# SH_input_2.net
KiCad netlist of a schematic drawn in EasyEDA
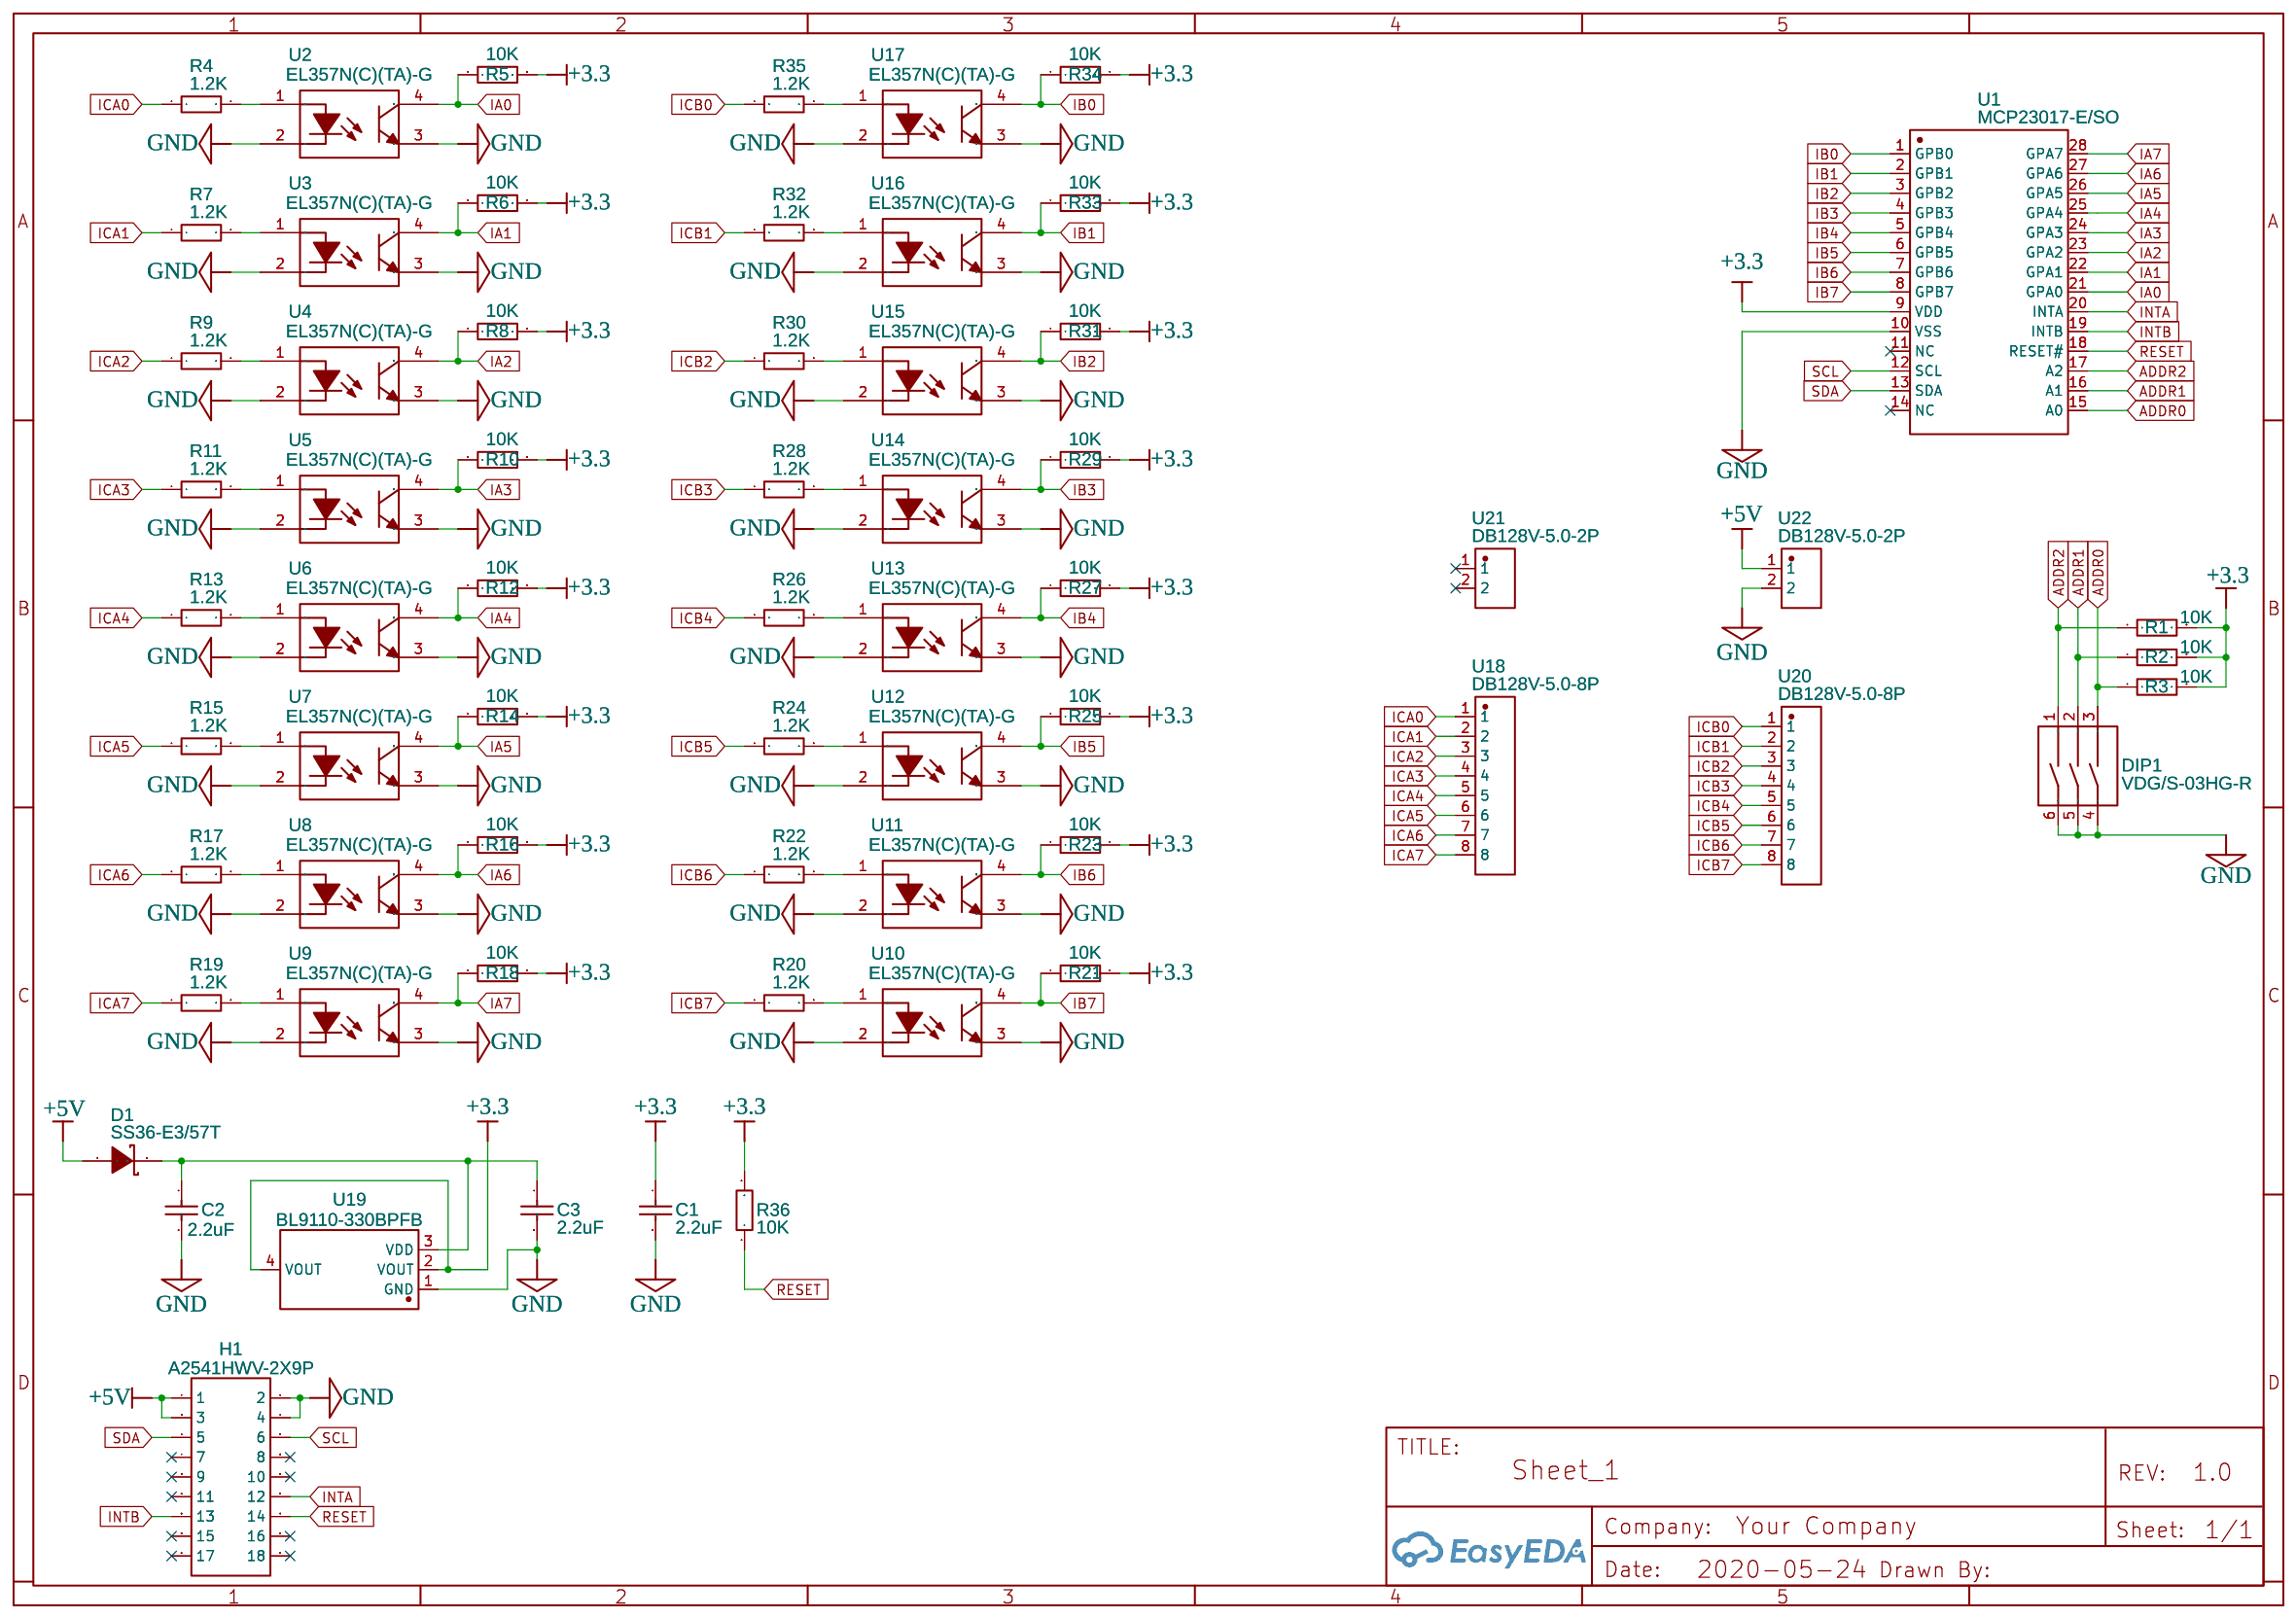
[diagram p0: schematic sheet]

(export (version "E")
  (design (tool "Eeschema 10.0.6"))
  (components
    (comp (ref "C1")
      (value "2.2uF")
      (fields
        (field (name "BOM_Manufacturer Part") "CL31B225KBHNNNE")
        (field (name "BOM_Supplier Part") "C50254")
      )
      (libsource (lib "") (part "CL31B225KBHNNNE"))
    )
    (comp (ref "C2")
      (value "2.2uF")
      (fields
        (field (name "BOM_Manufacturer Part") "CL31B225KBHNNNE")
        (field (name "BOM_Supplier Part") "C50254")
      )
      (libsource (lib "") (part "CL31B225KBHNNNE"))
    )
    (comp (ref "C3")
      (value "2.2uF")
      (fields
        (field (name "BOM_Manufacturer Part") "CL31B225KBHNNNE")
        (field (name "BOM_Supplier Part") "C50254")
      )
      (libsource (lib "") (part "CL31B225KBHNNNE"))
    )
    (comp (ref "D1")
      (value "SS36-E3/57T")
      (fields (field (name "BOM_Supplier Part") "C35722"))
      (libsource (lib "") (part "SS36-E3/57T"))
    )
    (comp (ref "DIP1")
      (value "VDG/S-03HG-R")
      (fields (field (name "BOM_Supplier Part") "C52648"))
      (libsource (lib "") (part "VDG/S-03HG-R"))
    )
    (comp (ref "H1")
      (value "A2541HWV-2X9P")
      (fields
        (field (name "BOM_Manufacturer Part") "A2541HWV-2x9P")
        (field (name "BOM_Supplier Part") "C239349")
      )
      (libsource (lib "") (part "A2541HWV-2X9P"))
    )
    (comp (ref "R1")
      (value "10K")
      (fields
        (field (name "BOM_Manufacturer Part") "0603WAF1002T5E")
        (field (name "BOM_Supplier Part") "C25804")
      )
      (libsource (lib "") (part "0603WAF1002T5E"))
    )
    (comp (ref "R2")
      (value "10K")
      (fields
        (field (name "BOM_Manufacturer Part") "0603WAF1002T5E")
        (field (name "BOM_Supplier Part") "C25804")
      )
      (libsource (lib "") (part "0603WAF1002T5E"))
    )
    (comp (ref "R3")
      (value "10K")
      (fields
        (field (name "BOM_Manufacturer Part") "0603WAF1002T5E")
        (field (name "BOM_Supplier Part") "C25804")
      )
      (libsource (lib "") (part "0603WAF1002T5E"))
    )
    (comp (ref "R4")
      (value "1.2K")
      (fields
        (field (name "BOM_Manufacturer Part") "0603WAF1201T5E")
        (field (name "BOM_Supplier Part") "C22765")
      )
      (libsource (lib "") (part "0603WAF1201T5E"))
    )
    (comp (ref "R5")
      (value "10K")
      (fields
        (field (name "BOM_Manufacturer Part") "0603WAF1002T5E")
        (field (name "BOM_Supplier Part") "C25804")
      )
      (libsource (lib "") (part "0603WAF1002T5E"))
    )
    (comp (ref "R6")
      (value "10K")
      (fields
        (field (name "BOM_Manufacturer Part") "0603WAF1002T5E")
        (field (name "BOM_Supplier Part") "C25804")
      )
      (libsource (lib "") (part "0603WAF1002T5E"))
    )
    (comp (ref "R7")
      (value "1.2K")
      (fields
        (field (name "BOM_Manufacturer Part") "0603WAF1201T5E")
        (field (name "BOM_Supplier Part") "C22765")
      )
      (libsource (lib "") (part "0603WAF1201T5E"))
    )
    (comp (ref "R8")
      (value "10K")
      (fields
        (field (name "BOM_Manufacturer Part") "0603WAF1002T5E")
        (field (name "BOM_Supplier Part") "C25804")
      )
      (libsource (lib "") (part "0603WAF1002T5E"))
    )
    (comp (ref "R9")
      (value "1.2K")
      (fields
        (field (name "BOM_Manufacturer Part") "0603WAF1201T5E")
        (field (name "BOM_Supplier Part") "C22765")
      )
      (libsource (lib "") (part "0603WAF1201T5E"))
    )
    (comp (ref "R10")
      (value "10K")
      (fields
        (field (name "BOM_Manufacturer Part") "0603WAF1002T5E")
        (field (name "BOM_Supplier Part") "C25804")
      )
      (libsource (lib "") (part "0603WAF1002T5E"))
    )
    (comp (ref "R11")
      (value "1.2K")
      (fields
        (field (name "BOM_Manufacturer Part") "0603WAF1201T5E")
        (field (name "BOM_Supplier Part") "C22765")
      )
      (libsource (lib "") (part "0603WAF1201T5E"))
    )
    (comp (ref "R12")
      (value "10K")
      (fields
        (field (name "BOM_Manufacturer Part") "0603WAF1002T5E")
        (field (name "BOM_Supplier Part") "C25804")
      )
      (libsource (lib "") (part "0603WAF1002T5E"))
    )
    (comp (ref "R13")
      (value "1.2K")
      (fields
        (field (name "BOM_Manufacturer Part") "0603WAF1201T5E")
        (field (name "BOM_Supplier Part") "C22765")
      )
      (libsource (lib "") (part "0603WAF1201T5E"))
    )
    (comp (ref "R14")
      (value "10K")
      (fields
        (field (name "BOM_Manufacturer Part") "0603WAF1002T5E")
        (field (name "BOM_Supplier Part") "C25804")
      )
      (libsource (lib "") (part "0603WAF1002T5E"))
    )
    (comp (ref "R15")
      (value "1.2K")
      (fields
        (field (name "BOM_Manufacturer Part") "0603WAF1201T5E")
        (field (name "BOM_Supplier Part") "C22765")
      )
      (libsource (lib "") (part "0603WAF1201T5E"))
    )
    (comp (ref "R16")
      (value "10K")
      (fields
        (field (name "BOM_Manufacturer Part") "0603WAF1002T5E")
        (field (name "BOM_Supplier Part") "C25804")
      )
      (libsource (lib "") (part "0603WAF1002T5E"))
    )
    (comp (ref "R17")
      (value "1.2K")
      (fields
        (field (name "BOM_Manufacturer Part") "0603WAF1201T5E")
        (field (name "BOM_Supplier Part") "C22765")
      )
      (libsource (lib "") (part "0603WAF1201T5E"))
    )
    (comp (ref "R18")
      (value "10K")
      (fields
        (field (name "BOM_Manufacturer Part") "0603WAF1002T5E")
        (field (name "BOM_Supplier Part") "C25804")
      )
      (libsource (lib "") (part "0603WAF1002T5E"))
    )
    (comp (ref "R19")
      (value "1.2K")
      (fields
        (field (name "BOM_Manufacturer Part") "0603WAF1201T5E")
        (field (name "BOM_Supplier Part") "C22765")
      )
      (libsource (lib "") (part "0603WAF1201T5E"))
    )
    (comp (ref "R20")
      (value "1.2K")
      (fields
        (field (name "BOM_Manufacturer Part") "0603WAF1201T5E")
        (field (name "BOM_Supplier Part") "C22765")
      )
      (libsource (lib "") (part "0603WAF1201T5E"))
    )
    (comp (ref "R21")
      (value "10K")
      (fields
        (field (name "BOM_Manufacturer Part") "0603WAF1002T5E")
        (field (name "BOM_Supplier Part") "C25804")
      )
      (libsource (lib "") (part "0603WAF1002T5E"))
    )
    (comp (ref "R22")
      (value "1.2K")
      (fields
        (field (name "BOM_Manufacturer Part") "0603WAF1201T5E")
        (field (name "BOM_Supplier Part") "C22765")
      )
      (libsource (lib "") (part "0603WAF1201T5E"))
    )
    (comp (ref "R23")
      (value "10K")
      (fields
        (field (name "BOM_Manufacturer Part") "0603WAF1002T5E")
        (field (name "BOM_Supplier Part") "C25804")
      )
      (libsource (lib "") (part "0603WAF1002T5E"))
    )
    (comp (ref "R24")
      (value "1.2K")
      (fields
        (field (name "BOM_Manufacturer Part") "0603WAF1201T5E")
        (field (name "BOM_Supplier Part") "C22765")
      )
      (libsource (lib "") (part "0603WAF1201T5E"))
    )
    (comp (ref "R25")
      (value "10K")
      (fields
        (field (name "BOM_Manufacturer Part") "0603WAF1002T5E")
        (field (name "BOM_Supplier Part") "C25804")
      )
      (libsource (lib "") (part "0603WAF1002T5E"))
    )
    (comp (ref "R26")
      (value "1.2K")
      (fields
        (field (name "BOM_Manufacturer Part") "0603WAF1201T5E")
        (field (name "BOM_Supplier Part") "C22765")
      )
      (libsource (lib "") (part "0603WAF1201T5E"))
    )
    (comp (ref "R27")
      (value "10K")
      (fields
        (field (name "BOM_Manufacturer Part") "0603WAF1002T5E")
        (field (name "BOM_Supplier Part") "C25804")
      )
      (libsource (lib "") (part "0603WAF1002T5E"))
    )
    (comp (ref "R28")
      (value "1.2K")
      (fields
        (field (name "BOM_Manufacturer Part") "0603WAF1201T5E")
        (field (name "BOM_Supplier Part") "C22765")
      )
      (libsource (lib "") (part "0603WAF1201T5E"))
    )
    (comp (ref "R29")
      (value "10K")
      (fields
        (field (name "BOM_Manufacturer Part") "0603WAF1002T5E")
        (field (name "BOM_Supplier Part") "C25804")
      )
      (libsource (lib "") (part "0603WAF1002T5E"))
    )
    (comp (ref "R30")
      (value "1.2K")
      (fields
        (field (name "BOM_Manufacturer Part") "0603WAF1201T5E")
        (field (name "BOM_Supplier Part") "C22765")
      )
      (libsource (lib "") (part "0603WAF1201T5E"))
    )
    (comp (ref "R31")
      (value "10K")
      (fields
        (field (name "BOM_Manufacturer Part") "0603WAF1002T5E")
        (field (name "BOM_Supplier Part") "C25804")
      )
      (libsource (lib "") (part "0603WAF1002T5E"))
    )
    (comp (ref "R32")
      (value "1.2K")
      (fields
        (field (name "BOM_Manufacturer Part") "0603WAF1201T5E")
        (field (name "BOM_Supplier Part") "C22765")
      )
      (libsource (lib "") (part "0603WAF1201T5E"))
    )
    (comp (ref "R33")
      (value "10K")
      (fields
        (field (name "BOM_Manufacturer Part") "0603WAF1002T5E")
        (field (name "BOM_Supplier Part") "C25804")
      )
      (libsource (lib "") (part "0603WAF1002T5E"))
    )
    (comp (ref "R34")
      (value "10K")
      (fields
        (field (name "BOM_Manufacturer Part") "0603WAF1002T5E")
        (field (name "BOM_Supplier Part") "C25804")
      )
      (libsource (lib "") (part "0603WAF1002T5E"))
    )
    (comp (ref "R35")
      (value "1.2K")
      (fields
        (field (name "BOM_Manufacturer Part") "0603WAF1201T5E")
        (field (name "BOM_Supplier Part") "C22765")
      )
      (libsource (lib "") (part "0603WAF1201T5E"))
    )
    (comp (ref "R36")
      (value "10K")
      (fields
        (field (name "BOM_Manufacturer Part") "0603WAF1002T5E")
        (field (name "BOM_Supplier Part") "C25804")
      )
      (libsource (lib "") (part "0603WAF1002T5E_1"))
    )
    (comp (ref "U1")
      (value "MCP23017-E/SO")
      (fields (field (name "BOM_Supplier Part") "C47023"))
      (libsource (lib "") (part "MCP23017-E/SO"))
    )
    (comp (ref "U2")
      (value "EL357N(C)(TA)-G")
      (fields (field (name "BOM_Supplier Part") "C29981"))
      (libsource (lib "") (part "EL357N(C)(TA)-G"))
    )
    (comp (ref "U3")
      (value "EL357N(C)(TA)-G")
      (fields (field (name "BOM_Supplier Part") "C29981"))
      (libsource (lib "") (part "EL357N(C)(TA)-G"))
    )
    (comp (ref "U4")
      (value "EL357N(C)(TA)-G")
      (fields (field (name "BOM_Supplier Part") "C29981"))
      (libsource (lib "") (part "EL357N(C)(TA)-G"))
    )
    (comp (ref "U5")
      (value "EL357N(C)(TA)-G")
      (fields (field (name "BOM_Supplier Part") "C29981"))
      (libsource (lib "") (part "EL357N(C)(TA)-G"))
    )
    (comp (ref "U6")
      (value "EL357N(C)(TA)-G")
      (fields (field (name "BOM_Supplier Part") "C29981"))
      (libsource (lib "") (part "EL357N(C)(TA)-G"))
    )
    (comp (ref "U7")
      (value "EL357N(C)(TA)-G")
      (fields (field (name "BOM_Supplier Part") "C29981"))
      (libsource (lib "") (part "EL357N(C)(TA)-G"))
    )
    (comp (ref "U8")
      (value "EL357N(C)(TA)-G")
      (fields (field (name "BOM_Supplier Part") "C29981"))
      (libsource (lib "") (part "EL357N(C)(TA)-G"))
    )
    (comp (ref "U9")
      (value "EL357N(C)(TA)-G")
      (fields (field (name "BOM_Supplier Part") "C29981"))
      (libsource (lib "") (part "EL357N(C)(TA)-G"))
    )
    (comp (ref "U10")
      (value "EL357N(C)(TA)-G")
      (fields (field (name "BOM_Supplier Part") "C29981"))
      (libsource (lib "") (part "EL357N(C)(TA)-G"))
    )
    (comp (ref "U11")
      (value "EL357N(C)(TA)-G")
      (fields (field (name "BOM_Supplier Part") "C29981"))
      (libsource (lib "") (part "EL357N(C)(TA)-G"))
    )
    (comp (ref "U12")
      (value "EL357N(C)(TA)-G")
      (fields (field (name "BOM_Supplier Part") "C29981"))
      (libsource (lib "") (part "EL357N(C)(TA)-G"))
    )
    (comp (ref "U13")
      (value "EL357N(C)(TA)-G")
      (fields (field (name "BOM_Supplier Part") "C29981"))
      (libsource (lib "") (part "EL357N(C)(TA)-G"))
    )
    (comp (ref "U14")
      (value "EL357N(C)(TA)-G")
      (fields (field (name "BOM_Supplier Part") "C29981"))
      (libsource (lib "") (part "EL357N(C)(TA)-G"))
    )
    (comp (ref "U15")
      (value "EL357N(C)(TA)-G")
      (fields (field (name "BOM_Supplier Part") "C29981"))
      (libsource (lib "") (part "EL357N(C)(TA)-G"))
    )
    (comp (ref "U16")
      (value "EL357N(C)(TA)-G")
      (fields (field (name "BOM_Supplier Part") "C29981"))
      (libsource (lib "") (part "EL357N(C)(TA)-G"))
    )
    (comp (ref "U17")
      (value "EL357N(C)(TA)-G")
      (fields (field (name "BOM_Supplier Part") "C29981"))
      (libsource (lib "") (part "EL357N(C)(TA)-G"))
    )
    (comp (ref "U18")
      (value "DB128V-5.0-8P")
      (fields (field (name "BOM_Supplier Part") "C395863"))
      (libsource (lib "") (part "DB128V-5.0-8P"))
    )
    (comp (ref "U19")
      (value "BL9110-330BPFB")
      (fields (field (name "BOM_Supplier Part") "C169246"))
      (libsource (lib "") (part "BL9110-330BPFB"))
    )
    (comp (ref "U20")
      (value "DB128V-5.0-8P")
      (fields (field (name "BOM_Supplier Part") "C395863"))
      (libsource (lib "") (part "DB128V-5.0-8P"))
    )
    (comp (ref "U21")
      (value "DB128V-5.0-2P")
      (fields (field (name "BOM_Supplier Part") "C395860"))
      (libsource (lib "") (part "DB128V-5.0-2P"))
    )
    (comp (ref "U22")
      (value "DB128V-5.0-2P")
      (fields (field (name "BOM_Supplier Part") "C395860"))
      (libsource (lib "") (part "DB128V-5.0-2P"))
    )
  )
  (nets
    (net (code "1") (name "+3.3") (class "Default")
      (node (ref "C1") (pin "1") (pinfunction "1_1") (pintype "input"))
      (node (ref "R1") (pin "2") (pinfunction "2_2") (pintype "input"))
      (node (ref "R10") (pin "2") (pinfunction "2_2") (pintype "input"))
      (node (ref "R12") (pin "2") (pinfunction "2_2") (pintype "input"))
      (node (ref "R14") (pin "2") (pinfunction "2_2") (pintype "input"))
      (node (ref "R16") (pin "2") (pinfunction "2_2") (pintype "input"))
      (node (ref "R18") (pin "2") (pinfunction "2_2") (pintype "input"))
      (node (ref "R2") (pin "2") (pinfunction "2_2") (pintype "input"))
      (node (ref "R21") (pin "2") (pinfunction "2_2") (pintype "input"))
      (node (ref "R23") (pin "2") (pinfunction "2_2") (pintype "input"))
      (node (ref "R25") (pin "2") (pinfunction "2_2") (pintype "input"))
      (node (ref "R27") (pin "2") (pinfunction "2_2") (pintype "input"))
      (node (ref "R29") (pin "2") (pinfunction "2_2") (pintype "input"))
      (node (ref "R3") (pin "2") (pinfunction "2_2") (pintype "input"))
      (node (ref "R31") (pin "2") (pinfunction "2_2") (pintype "input"))
      (node (ref "R33") (pin "2") (pinfunction "2_2") (pintype "input"))
      (node (ref "R34") (pin "2") (pinfunction "2_2") (pintype "input"))
      (node (ref "R36") (pin "2") (pinfunction "2_2") (pintype "input"))
      (node (ref "R5") (pin "2") (pinfunction "2_2") (pintype "input"))
      (node (ref "R6") (pin "2") (pinfunction "2_2") (pintype "input"))
      (node (ref "R8") (pin "2") (pinfunction "2_2") (pintype "input"))
      (node (ref "U1") (pin "9") (pinfunction "VDD_9") (pintype "unspecified"))
      (node (ref "U19") (pin "2") (pinfunction "VOUT_2") (pintype "unspecified"))
      (node (ref "U19") (pin "4") (pinfunction "VOUT_4") (pintype "unspecified"))
    )
    (net (code "2") (name "+5V") (class "Default")
      (node (ref "D1") (pin "1") (pinfunction "A_1") (pintype "unspecified"))
      (node (ref "H1") (pin "1") (pinfunction "1_1") (pintype "input"))
      (node (ref "H1") (pin "3") (pinfunction "3_3") (pintype "input"))
      (node (ref "U22") (pin "1") (pinfunction "1_1") (pintype "unspecified"))
    )
    (net (code "3") (name "ADDR0") (class "Default")
      (node (ref "DIP1") (pin "3") (pinfunction "3_3") (pintype "unspecified"))
      (node (ref "R3") (pin "1") (pinfunction "1_1") (pintype "input"))
      (node (ref "U1") (pin "15") (pinfunction "A0_15") (pintype "unspecified"))
    )
    (net (code "4") (name "ADDR1") (class "Default")
      (node (ref "DIP1") (pin "2") (pinfunction "2_2") (pintype "unspecified"))
      (node (ref "R2") (pin "1") (pinfunction "1_1") (pintype "input"))
      (node (ref "U1") (pin "16") (pinfunction "A1_16") (pintype "unspecified"))
    )
    (net (code "5") (name "ADDR2") (class "Default")
      (node (ref "DIP1") (pin "1") (pinfunction "1_1") (pintype "unspecified"))
      (node (ref "R1") (pin "1") (pinfunction "1_1") (pintype "input"))
      (node (ref "U1") (pin "17") (pinfunction "A2_17") (pintype "unspecified"))
    )
    (net (code "6") (name "GND") (class "Default")
      (node (ref "C1") (pin "2") (pinfunction "2_2") (pintype "input"))
      (node (ref "C2") (pin "2") (pinfunction "2_2") (pintype "input"))
      (node (ref "C3") (pin "2") (pinfunction "2_2") (pintype "input"))
      (node (ref "DIP1") (pin "4") (pinfunction "4_4") (pintype "unspecified"))
      (node (ref "DIP1") (pin "5") (pinfunction "5_5") (pintype "unspecified"))
      (node (ref "DIP1") (pin "6") (pinfunction "6_6") (pintype "unspecified"))
      (node (ref "H1") (pin "2") (pinfunction "2_2") (pintype "input"))
      (node (ref "H1") (pin "4") (pinfunction "4_4") (pintype "input"))
      (node (ref "U1") (pin "10") (pinfunction "VSS_10") (pintype "unspecified"))
      (node (ref "U10") (pin "2") (pinfunction "CAT_2") (pintype "unspecified"))
      (node (ref "U10") (pin "3") (pinfunction "EM_3") (pintype "unspecified"))
      (node (ref "U11") (pin "2") (pinfunction "CAT_2") (pintype "unspecified"))
      (node (ref "U11") (pin "3") (pinfunction "EM_3") (pintype "unspecified"))
      (node (ref "U12") (pin "2") (pinfunction "CAT_2") (pintype "unspecified"))
      (node (ref "U12") (pin "3") (pinfunction "EM_3") (pintype "unspecified"))
      (node (ref "U13") (pin "2") (pinfunction "CAT_2") (pintype "unspecified"))
      (node (ref "U13") (pin "3") (pinfunction "EM_3") (pintype "unspecified"))
      (node (ref "U14") (pin "2") (pinfunction "CAT_2") (pintype "unspecified"))
      (node (ref "U14") (pin "3") (pinfunction "EM_3") (pintype "unspecified"))
      (node (ref "U15") (pin "2") (pinfunction "CAT_2") (pintype "unspecified"))
      (node (ref "U15") (pin "3") (pinfunction "EM_3") (pintype "unspecified"))
      (node (ref "U16") (pin "2") (pinfunction "CAT_2") (pintype "unspecified"))
      (node (ref "U16") (pin "3") (pinfunction "EM_3") (pintype "unspecified"))
      (node (ref "U17") (pin "2") (pinfunction "CAT_2") (pintype "unspecified"))
      (node (ref "U17") (pin "3") (pinfunction "EM_3") (pintype "unspecified"))
      (node (ref "U19") (pin "1") (pinfunction "GND_1") (pintype "unspecified"))
      (node (ref "U2") (pin "2") (pinfunction "CAT_2") (pintype "unspecified"))
      (node (ref "U2") (pin "3") (pinfunction "EM_3") (pintype "unspecified"))
      (node (ref "U22") (pin "2") (pinfunction "2_2") (pintype "unspecified"))
      (node (ref "U3") (pin "2") (pinfunction "CAT_2") (pintype "unspecified"))
      (node (ref "U3") (pin "3") (pinfunction "EM_3") (pintype "unspecified"))
      (node (ref "U4") (pin "2") (pinfunction "CAT_2") (pintype "unspecified"))
      (node (ref "U4") (pin "3") (pinfunction "EM_3") (pintype "unspecified"))
      (node (ref "U5") (pin "2") (pinfunction "CAT_2") (pintype "unspecified"))
      (node (ref "U5") (pin "3") (pinfunction "EM_3") (pintype "unspecified"))
      (node (ref "U6") (pin "2") (pinfunction "CAT_2") (pintype "unspecified"))
      (node (ref "U6") (pin "3") (pinfunction "EM_3") (pintype "unspecified"))
      (node (ref "U7") (pin "2") (pinfunction "CAT_2") (pintype "unspecified"))
      (node (ref "U7") (pin "3") (pinfunction "EM_3") (pintype "unspecified"))
      (node (ref "U8") (pin "2") (pinfunction "CAT_2") (pintype "unspecified"))
      (node (ref "U8") (pin "3") (pinfunction "EM_3") (pintype "unspecified"))
      (node (ref "U9") (pin "2") (pinfunction "CAT_2") (pintype "unspecified"))
      (node (ref "U9") (pin "3") (pinfunction "EM_3") (pintype "unspecified"))
    )
    (net (code "7") (name "IA0") (class "Default")
      (node (ref "R5") (pin "1") (pinfunction "1_1") (pintype "input"))
      (node (ref "U1") (pin "21") (pinfunction "GPA0_21") (pintype "unspecified"))
      (node (ref "U2") (pin "4") (pinfunction "COL_4") (pintype "unspecified"))
    )
    (net (code "8") (name "IA1") (class "Default")
      (node (ref "R6") (pin "1") (pinfunction "1_1") (pintype "input"))
      (node (ref "U1") (pin "22") (pinfunction "GPA1_22") (pintype "unspecified"))
      (node (ref "U3") (pin "4") (pinfunction "COL_4") (pintype "unspecified"))
    )
    (net (code "9") (name "IA2") (class "Default")
      (node (ref "R8") (pin "1") (pinfunction "1_1") (pintype "input"))
      (node (ref "U1") (pin "23") (pinfunction "GPA2_23") (pintype "unspecified"))
      (node (ref "U4") (pin "4") (pinfunction "COL_4") (pintype "unspecified"))
    )
    (net (code "10") (name "IA3") (class "Default")
      (node (ref "R10") (pin "1") (pinfunction "1_1") (pintype "input"))
      (node (ref "U1") (pin "24") (pinfunction "GPA3_24") (pintype "unspecified"))
      (node (ref "U5") (pin "4") (pinfunction "COL_4") (pintype "unspecified"))
    )
    (net (code "11") (name "IA4") (class "Default")
      (node (ref "R12") (pin "1") (pinfunction "1_1") (pintype "input"))
      (node (ref "U1") (pin "25") (pinfunction "GPA4_25") (pintype "unspecified"))
      (node (ref "U6") (pin "4") (pinfunction "COL_4") (pintype "unspecified"))
    )
    (net (code "12") (name "IA5") (class "Default")
      (node (ref "R14") (pin "1") (pinfunction "1_1") (pintype "input"))
      (node (ref "U1") (pin "26") (pinfunction "GPA5_26") (pintype "unspecified"))
      (node (ref "U7") (pin "4") (pinfunction "COL_4") (pintype "unspecified"))
    )
    (net (code "13") (name "IA6") (class "Default")
      (node (ref "R16") (pin "1") (pinfunction "1_1") (pintype "input"))
      (node (ref "U1") (pin "27") (pinfunction "GPA6_27") (pintype "unspecified"))
      (node (ref "U8") (pin "4") (pinfunction "COL_4") (pintype "unspecified"))
    )
    (net (code "14") (name "IA7") (class "Default")
      (node (ref "R18") (pin "1") (pinfunction "1_1") (pintype "input"))
      (node (ref "U1") (pin "28") (pinfunction "GPA7_28") (pintype "unspecified"))
      (node (ref "U9") (pin "4") (pinfunction "COL_4") (pintype "unspecified"))
    )
    (net (code "15") (name "IB0") (class "Default")
      (node (ref "R34") (pin "1") (pinfunction "1_1") (pintype "input"))
      (node (ref "U1") (pin "1") (pinfunction "GPB0_1") (pintype "unspecified"))
      (node (ref "U17") (pin "4") (pinfunction "COL_4") (pintype "unspecified"))
    )
    (net (code "16") (name "IB1") (class "Default")
      (node (ref "R33") (pin "1") (pinfunction "1_1") (pintype "input"))
      (node (ref "U1") (pin "2") (pinfunction "GPB1_2") (pintype "unspecified"))
      (node (ref "U16") (pin "4") (pinfunction "COL_4") (pintype "unspecified"))
    )
    (net (code "17") (name "IB2") (class "Default")
      (node (ref "R31") (pin "1") (pinfunction "1_1") (pintype "input"))
      (node (ref "U1") (pin "3") (pinfunction "GPB2_3") (pintype "unspecified"))
      (node (ref "U15") (pin "4") (pinfunction "COL_4") (pintype "unspecified"))
    )
    (net (code "18") (name "IB3") (class "Default")
      (node (ref "R29") (pin "1") (pinfunction "1_1") (pintype "input"))
      (node (ref "U1") (pin "4") (pinfunction "GPB3_4") (pintype "unspecified"))
      (node (ref "U14") (pin "4") (pinfunction "COL_4") (pintype "unspecified"))
    )
    (net (code "19") (name "IB4") (class "Default")
      (node (ref "R27") (pin "1") (pinfunction "1_1") (pintype "input"))
      (node (ref "U1") (pin "5") (pinfunction "GPB4_5") (pintype "unspecified"))
      (node (ref "U13") (pin "4") (pinfunction "COL_4") (pintype "unspecified"))
    )
    (net (code "20") (name "IB5") (class "Default")
      (node (ref "R25") (pin "1") (pinfunction "1_1") (pintype "input"))
      (node (ref "U1") (pin "6") (pinfunction "GPB5_6") (pintype "unspecified"))
      (node (ref "U12") (pin "4") (pinfunction "COL_4") (pintype "unspecified"))
    )
    (net (code "21") (name "IB6") (class "Default")
      (node (ref "R23") (pin "1") (pinfunction "1_1") (pintype "input"))
      (node (ref "U1") (pin "7") (pinfunction "GPB6_7") (pintype "unspecified"))
      (node (ref "U11") (pin "4") (pinfunction "COL_4") (pintype "unspecified"))
    )
    (net (code "22") (name "IB7") (class "Default")
      (node (ref "R21") (pin "1") (pinfunction "1_1") (pintype "input"))
      (node (ref "U1") (pin "8") (pinfunction "GPB7_8") (pintype "unspecified"))
      (node (ref "U10") (pin "4") (pinfunction "COL_4") (pintype "unspecified"))
    )
    (net (code "23") (name "ICA0") (class "Default")
      (node (ref "R4") (pin "1") (pinfunction "1_1") (pintype "input"))
      (node (ref "U18") (pin "1") (pinfunction "1_1") (pintype "unspecified"))
    )
    (net (code "24") (name "ICA1") (class "Default")
      (node (ref "R7") (pin "1") (pinfunction "1_1") (pintype "input"))
      (node (ref "U18") (pin "2") (pinfunction "2_2") (pintype "unspecified"))
    )
    (net (code "25") (name "ICA2") (class "Default")
      (node (ref "R9") (pin "1") (pinfunction "1_1") (pintype "input"))
      (node (ref "U18") (pin "3") (pinfunction "3_3") (pintype "unspecified"))
    )
    (net (code "26") (name "ICA3") (class "Default")
      (node (ref "R11") (pin "1") (pinfunction "1_1") (pintype "input"))
      (node (ref "U18") (pin "4") (pinfunction "4_4") (pintype "unspecified"))
    )
    (net (code "27") (name "ICA4") (class "Default")
      (node (ref "R13") (pin "1") (pinfunction "1_1") (pintype "input"))
      (node (ref "U18") (pin "5") (pinfunction "5_5") (pintype "unspecified"))
    )
    (net (code "28") (name "ICA5") (class "Default")
      (node (ref "R15") (pin "1") (pinfunction "1_1") (pintype "input"))
      (node (ref "U18") (pin "6") (pinfunction "6_6") (pintype "unspecified"))
    )
    (net (code "29") (name "ICA6") (class "Default")
      (node (ref "R17") (pin "1") (pinfunction "1_1") (pintype "input"))
      (node (ref "U18") (pin "7") (pinfunction "7_7") (pintype "unspecified"))
    )
    (net (code "30") (name "ICA7") (class "Default")
      (node (ref "R19") (pin "1") (pinfunction "1_1") (pintype "input"))
      (node (ref "U18") (pin "8") (pinfunction "8_8") (pintype "unspecified"))
    )
    (net (code "31") (name "ICB0") (class "Default")
      (node (ref "R35") (pin "1") (pinfunction "1_1") (pintype "input"))
      (node (ref "U20") (pin "1") (pinfunction "1_1") (pintype "unspecified"))
    )
    (net (code "32") (name "ICB1") (class "Default")
      (node (ref "R32") (pin "1") (pinfunction "1_1") (pintype "input"))
      (node (ref "U20") (pin "2") (pinfunction "2_2") (pintype "unspecified"))
    )
    (net (code "33") (name "ICB2") (class "Default")
      (node (ref "R30") (pin "1") (pinfunction "1_1") (pintype "input"))
      (node (ref "U20") (pin "3") (pinfunction "3_3") (pintype "unspecified"))
    )
    (net (code "34") (name "ICB3") (class "Default")
      (node (ref "R28") (pin "1") (pinfunction "1_1") (pintype "input"))
      (node (ref "U20") (pin "4") (pinfunction "4_4") (pintype "unspecified"))
    )
    (net (code "35") (name "ICB4") (class "Default")
      (node (ref "R26") (pin "1") (pinfunction "1_1") (pintype "input"))
      (node (ref "U20") (pin "5") (pinfunction "5_5") (pintype "unspecified"))
    )
    (net (code "36") (name "ICB5") (class "Default")
      (node (ref "R24") (pin "1") (pinfunction "1_1") (pintype "input"))
      (node (ref "U20") (pin "6") (pinfunction "6_6") (pintype "unspecified"))
    )
    (net (code "37") (name "ICB6") (class "Default")
      (node (ref "R22") (pin "1") (pinfunction "1_1") (pintype "input"))
      (node (ref "U20") (pin "7") (pinfunction "7_7") (pintype "unspecified"))
    )
    (net (code "38") (name "ICB7") (class "Default")
      (node (ref "R20") (pin "1") (pinfunction "1_1") (pintype "input"))
      (node (ref "U20") (pin "8") (pinfunction "8_8") (pintype "unspecified"))
    )
    (net (code "39") (name "INTA") (class "Default")
      (node (ref "H1") (pin "12") (pinfunction "12_12") (pintype "input"))
      (node (ref "U1") (pin "20") (pinfunction "INTA_20") (pintype "unspecified"))
    )
    (net (code "40") (name "INTB") (class "Default")
      (node (ref "H1") (pin "13") (pinfunction "13_13") (pintype "input"))
      (node (ref "U1") (pin "19") (pinfunction "INTB_19") (pintype "unspecified"))
    )
    (net (code "41") (name "Net-(D1-K)") (class "Default")
      (node (ref "C2") (pin "1") (pinfunction "1_1") (pintype "input"))
      (node (ref "C3") (pin "1") (pinfunction "1_1") (pintype "input"))
      (node (ref "D1") (pin "2") (pinfunction "K_2") (pintype "unspecified"))
      (node (ref "U19") (pin "3") (pinfunction "VDD_3") (pintype "unspecified"))
    )
    (net (code "42") (name "Net-(U2-AN)") (class "Default")
      (node (ref "R4") (pin "2") (pinfunction "2_2") (pintype "input"))
      (node (ref "U2") (pin "1") (pinfunction "AN_1") (pintype "unspecified"))
    )
    (net (code "43") (name "Net-(U3-AN)") (class "Default")
      (node (ref "R7") (pin "2") (pinfunction "2_2") (pintype "input"))
      (node (ref "U3") (pin "1") (pinfunction "AN_1") (pintype "unspecified"))
    )
    (net (code "44") (name "Net-(U4-AN)") (class "Default")
      (node (ref "R9") (pin "2") (pinfunction "2_2") (pintype "input"))
      (node (ref "U4") (pin "1") (pinfunction "AN_1") (pintype "unspecified"))
    )
    (net (code "45") (name "Net-(U5-AN)") (class "Default")
      (node (ref "R11") (pin "2") (pinfunction "2_2") (pintype "input"))
      (node (ref "U5") (pin "1") (pinfunction "AN_1") (pintype "unspecified"))
    )
    (net (code "46") (name "Net-(U6-AN)") (class "Default")
      (node (ref "R13") (pin "2") (pinfunction "2_2") (pintype "input"))
      (node (ref "U6") (pin "1") (pinfunction "AN_1") (pintype "unspecified"))
    )
    (net (code "47") (name "Net-(U7-AN)") (class "Default")
      (node (ref "R15") (pin "2") (pinfunction "2_2") (pintype "input"))
      (node (ref "U7") (pin "1") (pinfunction "AN_1") (pintype "unspecified"))
    )
    (net (code "48") (name "Net-(U8-AN)") (class "Default")
      (node (ref "R17") (pin "2") (pinfunction "2_2") (pintype "input"))
      (node (ref "U8") (pin "1") (pinfunction "AN_1") (pintype "unspecified"))
    )
    (net (code "49") (name "Net-(U9-AN)") (class "Default")
      (node (ref "R19") (pin "2") (pinfunction "2_2") (pintype "input"))
      (node (ref "U9") (pin "1") (pinfunction "AN_1") (pintype "unspecified"))
    )
    (net (code "50") (name "Net-(U10-AN)") (class "Default")
      (node (ref "R20") (pin "2") (pinfunction "2_2") (pintype "input"))
      (node (ref "U10") (pin "1") (pinfunction "AN_1") (pintype "unspecified"))
    )
    (net (code "51") (name "Net-(U11-AN)") (class "Default")
      (node (ref "R22") (pin "2") (pinfunction "2_2") (pintype "input"))
      (node (ref "U11") (pin "1") (pinfunction "AN_1") (pintype "unspecified"))
    )
    (net (code "52") (name "Net-(U12-AN)") (class "Default")
      (node (ref "R24") (pin "2") (pinfunction "2_2") (pintype "input"))
      (node (ref "U12") (pin "1") (pinfunction "AN_1") (pintype "unspecified"))
    )
    (net (code "53") (name "Net-(U13-AN)") (class "Default")
      (node (ref "R26") (pin "2") (pinfunction "2_2") (pintype "input"))
      (node (ref "U13") (pin "1") (pinfunction "AN_1") (pintype "unspecified"))
    )
    (net (code "54") (name "Net-(U14-AN)") (class "Default")
      (node (ref "R28") (pin "2") (pinfunction "2_2") (pintype "input"))
      (node (ref "U14") (pin "1") (pinfunction "AN_1") (pintype "unspecified"))
    )
    (net (code "55") (name "Net-(U15-AN)") (class "Default")
      (node (ref "R30") (pin "2") (pinfunction "2_2") (pintype "input"))
      (node (ref "U15") (pin "1") (pinfunction "AN_1") (pintype "unspecified"))
    )
    (net (code "56") (name "Net-(U16-AN)") (class "Default")
      (node (ref "R32") (pin "2") (pinfunction "2_2") (pintype "input"))
      (node (ref "U16") (pin "1") (pinfunction "AN_1") (pintype "unspecified"))
    )
    (net (code "57") (name "Net-(U17-AN)") (class "Default")
      (node (ref "R35") (pin "2") (pinfunction "2_2") (pintype "input"))
      (node (ref "U17") (pin "1") (pinfunction "AN_1") (pintype "unspecified"))
    )
    (net (code "58") (name "RESET") (class "Default")
      (node (ref "H1") (pin "14") (pinfunction "14_14") (pintype "input"))
      (node (ref "R36") (pin "1") (pinfunction "1_1") (pintype "input"))
      (node (ref "U1") (pin "18") (pinfunction "RESET#_18") (pintype "unspecified"))
    )
    (net (code "59") (name "SCL") (class "Default")
      (node (ref "H1") (pin "6") (pinfunction "6_6") (pintype "input"))
      (node (ref "U1") (pin "12") (pinfunction "SCL_12") (pintype "unspecified"))
    )
    (net (code "60") (name "SDA") (class "Default")
      (node (ref "H1") (pin "5") (pinfunction "5_5") (pintype "input"))
      (node (ref "U1") (pin "13") (pinfunction "SDA_13") (pintype "unspecified"))
    )
    (net (code "61") (name "unconnected-(H1-Pad7)") (class "Default")
      (node (ref "H1") (pin "7") (pinfunction "7_7") (pintype "input+no_connect"))
    )
    (net (code "62") (name "unconnected-(H1-Pad8)") (class "Default")
      (node (ref "H1") (pin "8") (pinfunction "8_8") (pintype "input+no_connect"))
    )
    (net (code "63") (name "unconnected-(H1-Pad9)") (class "Default")
      (node (ref "H1") (pin "9") (pinfunction "9_9") (pintype "input+no_connect"))
    )
    (net (code "64") (name "unconnected-(H1-Pad10)") (class "Default")
      (node (ref "H1") (pin "10") (pinfunction "10_10") (pintype "input+no_connect"))
    )
    (net (code "65") (name "unconnected-(H1-Pad11)") (class "Default")
      (node (ref "H1") (pin "11") (pinfunction "11_11") (pintype "input+no_connect"))
    )
    (net (code "66") (name "unconnected-(H1-Pad15)") (class "Default")
      (node (ref "H1") (pin "15") (pinfunction "15_15") (pintype "input+no_connect"))
    )
    (net (code "67") (name "unconnected-(H1-Pad16)") (class "Default")
      (node (ref "H1") (pin "16") (pinfunction "16_16") (pintype "input+no_connect"))
    )
    (net (code "68") (name "unconnected-(H1-Pad17)") (class "Default")
      (node (ref "H1") (pin "17") (pinfunction "17_17") (pintype "input+no_connect"))
    )
    (net (code "69") (name "unconnected-(H1-Pad18)") (class "Default")
      (node (ref "H1") (pin "18") (pinfunction "18_18") (pintype "input+no_connect"))
    )
    (net (code "70") (name "unconnected-(U1-NC-Pad11)") (class "Default")
      (node (ref "U1") (pin "11") (pinfunction "NC_11") (pintype "unspecified+no_connect"))
    )
    (net (code "71") (name "unconnected-(U1-NC-Pad14)") (class "Default")
      (node (ref "U1") (pin "14") (pinfunction "NC_14") (pintype "unspecified+no_connect"))
    )
    (net (code "72") (name "unconnected-(U21-Pad1)") (class "Default")
      (node (ref "U21") (pin "1") (pinfunction "1_1") (pintype "unspecified+no_connect"))
    )
    (net (code "73") (name "unconnected-(U21-Pad2)") (class "Default")
      (node (ref "U21") (pin "2") (pinfunction "2_2") (pintype "unspecified+no_connect"))
    )
  )
)
